# M8830Ccpld.net
KiCad netlist of a schematic drawn in EAGLE
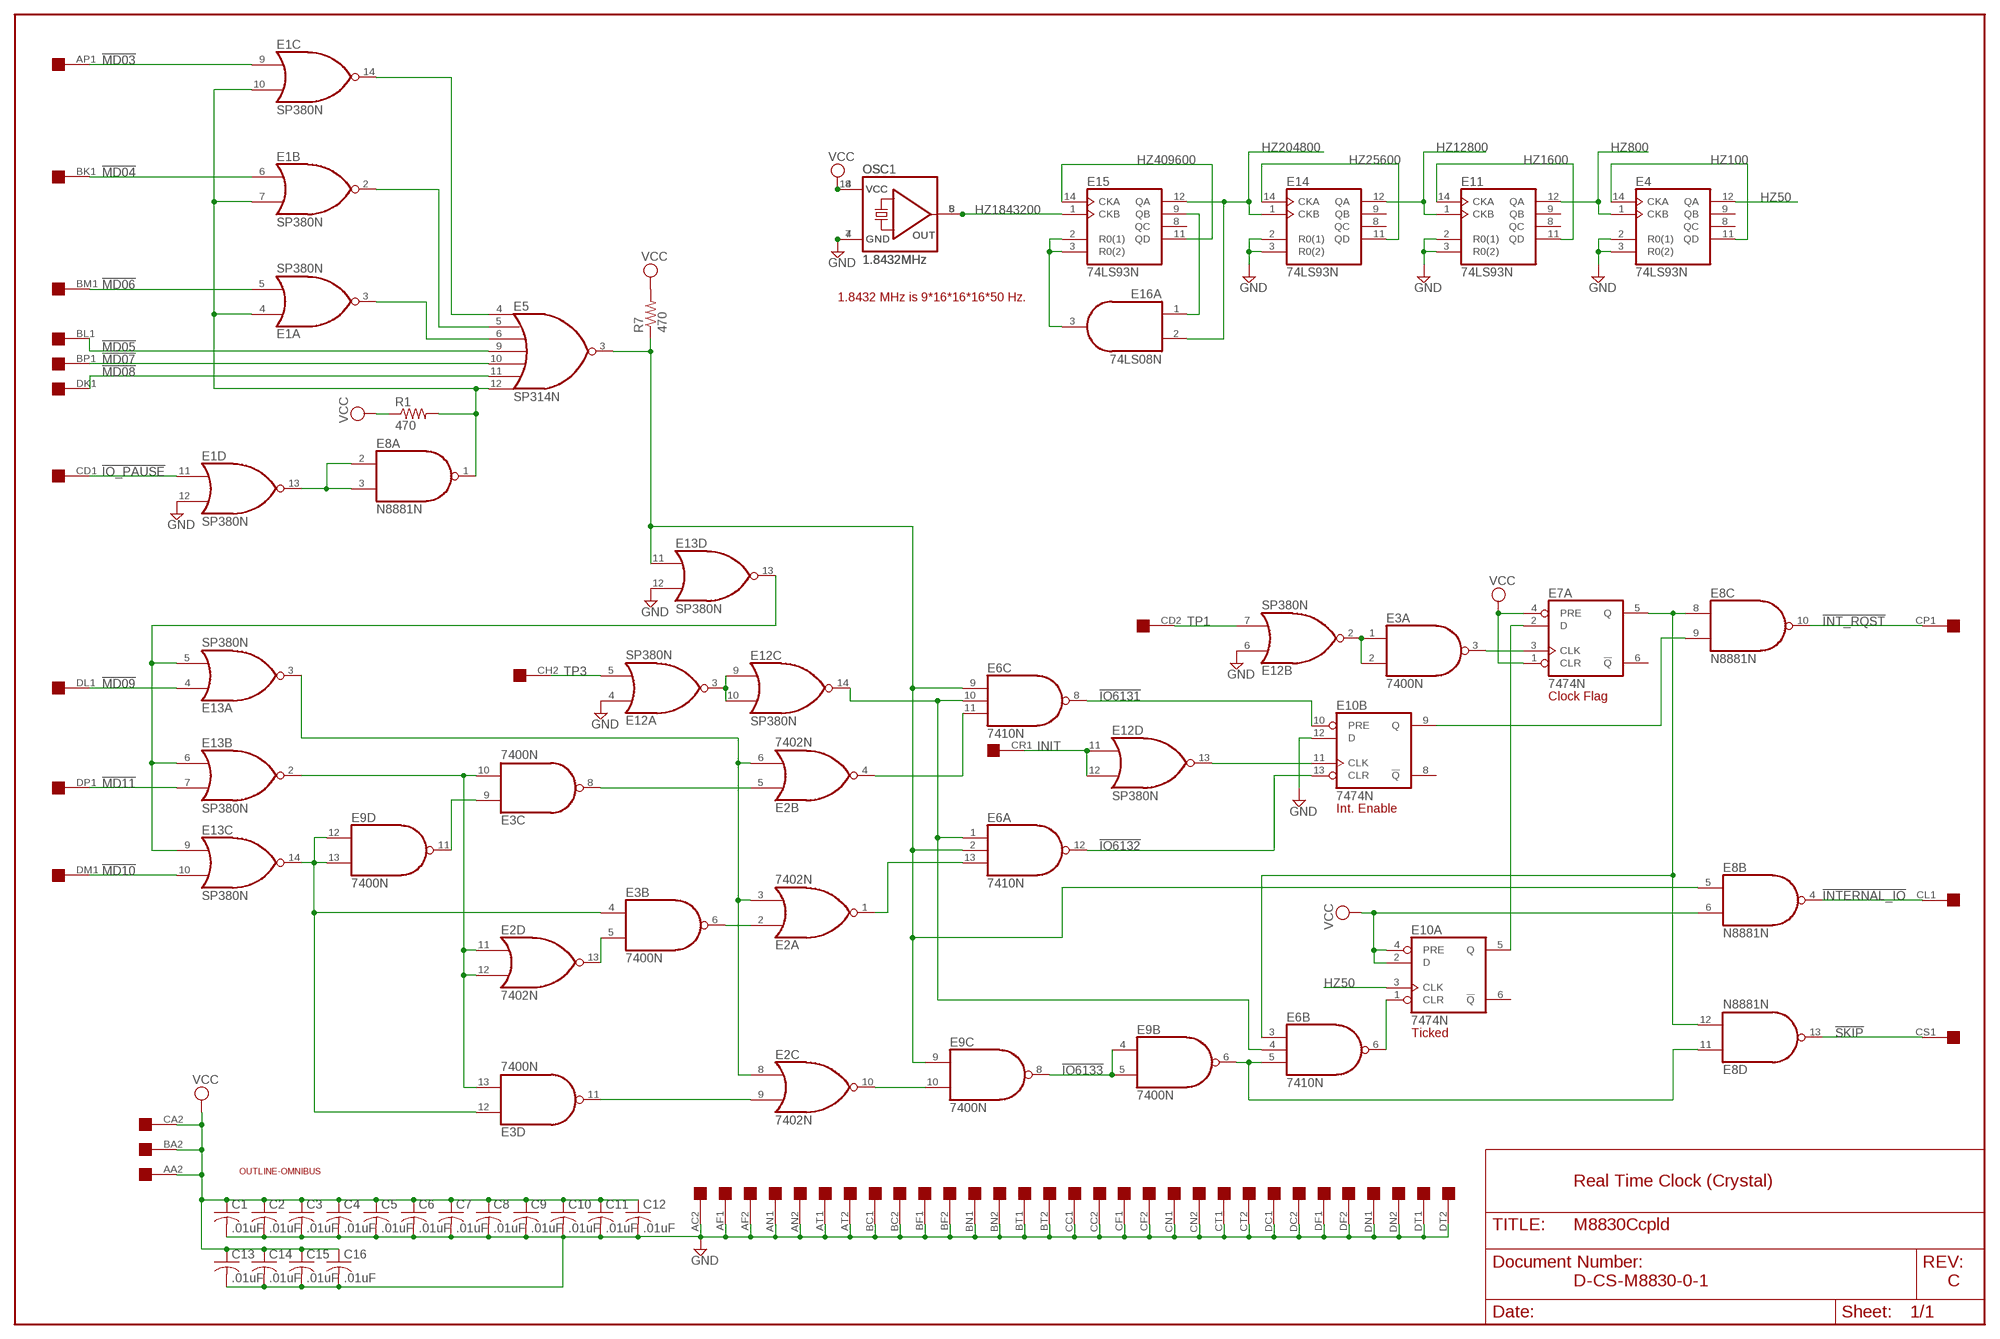
[diagram p0: schematic, sheet 1]

(export (version "E")
  (design (tool "Eeschema 10.0.6"))
  (components
    (comp (ref "C1")
      (value ".01uF")
      (footprint "eagle-import:C050-025X075")
      (libsource (lib "eagle-import") (part "C-US050-025X075"))
    )
    (comp (ref "C2")
      (value ".01uF")
      (footprint "eagle-import:C050-025X075")
      (libsource (lib "eagle-import") (part "C-US050-025X075"))
    )
    (comp (ref "C3")
      (value ".01uF")
      (footprint "eagle-import:C050-025X075")
      (libsource (lib "eagle-import") (part "C-US050-025X075"))
    )
    (comp (ref "C4")
      (value ".01uF")
      (footprint "eagle-import:C050-025X075")
      (libsource (lib "eagle-import") (part "C-US050-025X075"))
    )
    (comp (ref "C5")
      (value ".01uF")
      (footprint "eagle-import:C050-025X075")
      (libsource (lib "eagle-import") (part "C-US050-025X075"))
    )
    (comp (ref "C6")
      (value ".01uF")
      (footprint "eagle-import:C050-025X075")
      (libsource (lib "eagle-import") (part "C-US050-025X075"))
    )
    (comp (ref "C7")
      (value ".01uF")
      (footprint "eagle-import:C050-025X075")
      (libsource (lib "eagle-import") (part "C-US050-025X075"))
    )
    (comp (ref "C8")
      (value ".01uF")
      (footprint "eagle-import:C050-025X075")
      (libsource (lib "eagle-import") (part "C-US050-025X075"))
    )
    (comp (ref "C9")
      (value ".01uF")
      (footprint "eagle-import:C050-025X075")
      (libsource (lib "eagle-import") (part "C-US050-025X075"))
    )
    (comp (ref "C10")
      (value ".01uF")
      (footprint "eagle-import:C050-025X075")
      (libsource (lib "eagle-import") (part "C-US050-025X075"))
    )
    (comp (ref "C11")
      (value ".01uF")
      (footprint "eagle-import:C050-025X075")
      (libsource (lib "eagle-import") (part "C-US050-025X075"))
    )
    (comp (ref "C12")
      (value ".01uF")
      (footprint "eagle-import:C050-025X075")
      (libsource (lib "eagle-import") (part "C-US050-025X075"))
    )
    (comp (ref "C13")
      (value ".01uF")
      (footprint "eagle-import:C050-025X075")
      (libsource (lib "eagle-import") (part "C-US050-025X075"))
    )
    (comp (ref "C14")
      (value ".01uF")
      (footprint "eagle-import:C050-025X075")
      (libsource (lib "eagle-import") (part "C-US050-025X075"))
    )
    (comp (ref "C15")
      (value ".01uF")
      (footprint "eagle-import:C050-025X075")
      (libsource (lib "eagle-import") (part "C-US050-025X075"))
    )
    (comp (ref "C16")
      (value ".01uF")
      (footprint "eagle-import:C050-025X075")
      (libsource (lib "eagle-import") (part "C-US050-025X075"))
    )
    (comp (ref "E1")
      (value "SP380N")
      (footprint "eagle-import:DIL14")
      (libsource (lib "eagle-import") (part "SP380N"))
    )
    (comp (ref "E2")
      (value "7402N")
      (footprint "eagle-import:DIL14")
      (libsource (lib "eagle-import") (part "7402N"))
    )
    (comp (ref "E3")
      (value "7400N")
      (footprint "eagle-import:DIL14")
      (libsource (lib "eagle-import") (part "7400N"))
    )
    (comp (ref "E4")
      (value "74LS93N")
      (footprint "eagle-import:DIL14")
      (libsource (lib "eagle-import") (part "7493NLS"))
    )
    (comp (ref "E5")
      (value "SP314N")
      (footprint "eagle-import:DIL14")
      (libsource (lib "eagle-import") (part "SP314N"))
    )
    (comp (ref "E6")
      (value "7410N")
      (footprint "eagle-import:DIL14")
      (libsource (lib "eagle-import") (part "7410N"))
    )
    (comp (ref "E7")
      (value "7474N")
      (footprint "eagle-import:DIL14")
      (libsource (lib "eagle-import") (part "7474NS"))
    )
    (comp (ref "E8")
      (value "N8881N")
      (footprint "eagle-import:DIL14")
      (libsource (lib "eagle-import") (part "N8881N"))
    )
    (comp (ref "E9")
      (value "7400N")
      (footprint "eagle-import:DIL14")
      (libsource (lib "eagle-import") (part "7400N"))
    )
    (comp (ref "E10")
      (value "7474N")
      (footprint "eagle-import:DIL14")
      (libsource (lib "eagle-import") (part "7474NS"))
    )
    (comp (ref "E11")
      (value "74LS93N")
      (footprint "eagle-import:DIL14")
      (libsource (lib "eagle-import") (part "7493NLS"))
    )
    (comp (ref "E12")
      (value "SP380N")
      (footprint "eagle-import:DIL14")
      (libsource (lib "eagle-import") (part "SP380N"))
    )
    (comp (ref "E13")
      (value "SP380N")
      (footprint "eagle-import:DIL14")
      (libsource (lib "eagle-import") (part "SP380N"))
    )
    (comp (ref "E14")
      (value "74LS93N")
      (footprint "eagle-import:DIL14")
      (libsource (lib "eagle-import") (part "7493NLS"))
    )
    (comp (ref "E15")
      (value "74LS93N")
      (footprint "eagle-import:DIL14")
      (libsource (lib "eagle-import") (part "7493NLS"))
    )
    (comp (ref "E16")
      (value "74LS08N")
      (footprint "eagle-import:DIL14")
      (libsource (lib "eagle-import") (part "7408NLS"))
    )
    (comp (ref "EDGE")
      (value "QUAD")
      (footprint "eagle-import:EDGE-CON8")
      (libsource (lib "eagle-import") (part "QUAD"))
    )
    (comp (ref "OSC")
      (value "1.8432MHz")
      (footprint "eagle-import:DIL08S")
      (libsource (lib "eagle-import") (part "QG5460"))
    )
    (comp (ref "OSC1")
      (value "1.8432MHz")
      (footprint "eagle-import:DIL14S")
      (libsource (lib "eagle-import") (part "QG5860"))
    )
    (comp (ref "R1")
      (value "470")
      (footprint "eagle-import:0207_10")
      (libsource (lib "eagle-import") (part "R-US_0207/10"))
    )
    (comp (ref "R7")
      (value "470")
      (footprint "eagle-import:0207_10")
      (libsource (lib "eagle-import") (part "R-US_0207/10"))
    )
    (comp (ref "U$1")
      (value "OUTLINE-OMNIBUS")
      (footprint "eagle-import:OMNIBUS")
      (libsource (lib "eagle-import") (part "OUTLINE-OMNIBUS"))
    )
  )
  (nets
    (net (code "1") (name "/HZ50") (class "Default")
      (node (ref "E10") (pin "3") (pinfunction "CLK_3") (pintype "input"))
      (node (ref "E4") (pin "12") (pinfunction "QA_12") (pintype "output"))
    )
    (net (code "2") (name "/HZ100") (class "Default")
      (node (ref "E4") (pin "11") (pinfunction "QD_11") (pintype "output"))
      (node (ref "E4") (pin "14") (pinfunction "CKA_14") (pintype "input"))
    )
    (net (code "3") (name "/HZ800") (class "Default")
      (node (ref "E11") (pin "12") (pinfunction "QA_12") (pintype "output"))
      (node (ref "E4") (pin "1") (pinfunction "CKB_1") (pintype "input"))
    )
    (net (code "4") (name "/HZ1600") (class "Default")
      (node (ref "E11") (pin "11") (pinfunction "QD_11") (pintype "output"))
      (node (ref "E11") (pin "14") (pinfunction "CKA_14") (pintype "input"))
    )
    (net (code "5") (name "/HZ12800") (class "Default")
      (node (ref "E11") (pin "1") (pinfunction "CKB_1") (pintype "input"))
      (node (ref "E14") (pin "12") (pinfunction "QA_12") (pintype "output"))
    )
    (net (code "6") (name "/HZ25600") (class "Default")
      (node (ref "E14") (pin "11") (pinfunction "QD_11") (pintype "output"))
      (node (ref "E14") (pin "14") (pinfunction "CKA_14") (pintype "input"))
    )
    (net (code "7") (name "/HZ204800") (class "Default")
      (node (ref "E14") (pin "1") (pinfunction "CKB_1") (pintype "input"))
      (node (ref "E15") (pin "12") (pinfunction "QA_12") (pintype "output"))
      (node (ref "E16") (pin "2") (pinfunction "I1_2") (pintype "input"))
    )
    (net (code "8") (name "/HZ409600") (class "Default")
      (node (ref "E15") (pin "11") (pinfunction "QD_11") (pintype "output"))
      (node (ref "E15") (pin "14") (pinfunction "CKA_14") (pintype "input"))
    )
    (net (code "9") (name "/HZ1843200") (class "Default")
      (node (ref "E15") (pin "1") (pinfunction "CKB_1") (pintype "input"))
      (node (ref "OSC") (pin "5") (pinfunction "OUT_5") (pintype "output"))
      (node (ref "OSC1") (pin "8") (pinfunction "OUT_8") (pintype "output"))
    )
    (net (code "10") (name "/INIT") (class "Default")
      (node (ref "E12") (pin "11") (pinfunction "I0_11") (pintype "input"))
      (node (ref "E12") (pin "12") (pinfunction "I1_12") (pintype "input"))
      (node (ref "EDGE") (pin "CR1") (pinfunction "1_CR1") (pintype "bidirectional"))
    )
    (net (code "11") (name "/TP1") (class "Default")
      (node (ref "E12") (pin "7") (pinfunction "I1_7") (pintype "input"))
      (node (ref "EDGE") (pin "CD2") (pinfunction "1_CD2") (pintype "bidirectional"))
    )
    (net (code "12") (name "/TP3") (class "Default")
      (node (ref "E12") (pin "5") (pinfunction "I1_5") (pintype "input"))
      (node (ref "EDGE") (pin "CH2") (pinfunction "1_CH2") (pintype "bidirectional"))
    )
    (net (code "13") (name "/~{INTERNAL_IO}") (class "Default")
      (node (ref "E8") (pin "4") (pinfunction "O_4") (pintype "open_collector"))
      (node (ref "EDGE") (pin "CL1") (pinfunction "1_CL1") (pintype "bidirectional"))
    )
    (net (code "14") (name "/~{INT_RQST}") (class "Default")
      (node (ref "E8") (pin "10") (pinfunction "O_10") (pintype "open_collector"))
      (node (ref "EDGE") (pin "CP1") (pinfunction "1_CP1") (pintype "bidirectional"))
    )
    (net (code "15") (name "/~{IO6131}") (class "Default")
      (node (ref "E10") (pin "10") (pinfunction "PRE_10") (pintype "input"))
      (node (ref "E6") (pin "8") (pinfunction "O_8") (pintype "output"))
    )
    (net (code "16") (name "/~{IO6132}") (class "Default")
      (node (ref "E10") (pin "13") (pinfunction "CLR_13") (pintype "input"))
      (node (ref "E6") (pin "12") (pinfunction "O_12") (pintype "output"))
    )
    (net (code "17") (name "/~{IO6133}") (class "Default")
      (node (ref "E9") (pin "4") (pinfunction "I0_4") (pintype "input"))
      (node (ref "E9") (pin "5") (pinfunction "I1_5") (pintype "input"))
      (node (ref "E9") (pin "8") (pinfunction "O_8") (pintype "output"))
    )
    (net (code "18") (name "/~{IO_PAUSE}") (class "Default")
      (node (ref "E1") (pin "11") (pinfunction "I0_11") (pintype "input"))
      (node (ref "EDGE") (pin "CD1") (pinfunction "1_CD1") (pintype "bidirectional"))
    )
    (net (code "19") (name "/~{MD03}") (class "Default")
      (node (ref "E1") (pin "9") (pinfunction "I0_9") (pintype "input"))
      (node (ref "EDGE") (pin "AP1") (pinfunction "1_AP1") (pintype "bidirectional"))
    )
    (net (code "20") (name "/~{MD04}") (class "Default")
      (node (ref "E1") (pin "6") (pinfunction "I0_6") (pintype "input"))
      (node (ref "EDGE") (pin "BK1") (pinfunction "1_BK1") (pintype "bidirectional"))
    )
    (net (code "21") (name "/~{MD05}") (class "Default")
      (node (ref "E5") (pin "9") (pinfunction "I3_9") (pintype "input"))
      (node (ref "EDGE") (pin "BL1") (pinfunction "1_BL1") (pintype "bidirectional"))
    )
    (net (code "22") (name "/~{MD06}") (class "Default")
      (node (ref "E1") (pin "5") (pinfunction "I1_5") (pintype "input"))
      (node (ref "EDGE") (pin "BM1") (pinfunction "1_BM1") (pintype "bidirectional"))
    )
    (net (code "23") (name "/~{MD07}") (class "Default")
      (node (ref "E5") (pin "10") (pinfunction "I4_10") (pintype "input"))
      (node (ref "EDGE") (pin "BP1") (pinfunction "1_BP1") (pintype "bidirectional"))
    )
    (net (code "24") (name "/~{MD08}") (class "Default")
      (node (ref "E5") (pin "11") (pinfunction "I5_11") (pintype "input"))
      (node (ref "EDGE") (pin "DK1") (pinfunction "1_DK1") (pintype "bidirectional"))
    )
    (net (code "25") (name "/~{MD09}") (class "Default")
      (node (ref "E13") (pin "4") (pinfunction "I0_4") (pintype "input"))
      (node (ref "EDGE") (pin "DL1") (pinfunction "1_DL1") (pintype "bidirectional"))
    )
    (net (code "26") (name "/~{MD10}") (class "Default")
      (node (ref "E13") (pin "10") (pinfunction "I1_10") (pintype "input"))
      (node (ref "EDGE") (pin "DM1") (pinfunction "1_DM1") (pintype "bidirectional"))
    )
    (net (code "27") (name "/~{MD11}") (class "Default")
      (node (ref "E13") (pin "7") (pinfunction "I1_7") (pintype "input"))
      (node (ref "EDGE") (pin "DP1") (pinfunction "1_DP1") (pintype "bidirectional"))
    )
    (net (code "28") (name "/~{SKIP}") (class "Default")
      (node (ref "E8") (pin "13") (pinfunction "O_13") (pintype "open_collector"))
      (node (ref "EDGE") (pin "CS1") (pinfunction "1_CS1") (pintype "bidirectional"))
    )
    (net (code "29") (name "GND") (class "Default")
      (node (ref "C1") (pin "2") (pinfunction "2_2") (pintype "passive"))
      (node (ref "C10") (pin "2") (pinfunction "2_2") (pintype "passive"))
      (node (ref "C11") (pin "2") (pinfunction "2_2") (pintype "passive"))
      (node (ref "C12") (pin "2") (pinfunction "2_2") (pintype "passive"))
      (node (ref "C13") (pin "2") (pinfunction "2_2") (pintype "passive"))
      (node (ref "C14") (pin "2") (pinfunction "2_2") (pintype "passive"))
      (node (ref "C15") (pin "2") (pinfunction "2_2") (pintype "passive"))
      (node (ref "C16") (pin "2") (pinfunction "2_2") (pintype "passive"))
      (node (ref "C2") (pin "2") (pinfunction "2_2") (pintype "passive"))
      (node (ref "C3") (pin "2") (pinfunction "2_2") (pintype "passive"))
      (node (ref "C4") (pin "2") (pinfunction "2_2") (pintype "passive"))
      (node (ref "C5") (pin "2") (pinfunction "2_2") (pintype "passive"))
      (node (ref "C6") (pin "2") (pinfunction "2_2") (pintype "passive"))
      (node (ref "C7") (pin "2") (pinfunction "2_2") (pintype "passive"))
      (node (ref "C8") (pin "2") (pinfunction "2_2") (pintype "passive"))
      (node (ref "C9") (pin "2") (pinfunction "2_2") (pintype "passive"))
      (node (ref "E1") (pin "12") (pinfunction "I1_12") (pintype "input"))
      (node (ref "E10") (pin "12") (pinfunction "D_12") (pintype "input"))
      (node (ref "E11") (pin "2") (pinfunction "R0(1)_2") (pintype "input"))
      (node (ref "E11") (pin "3") (pinfunction "R0(2)_3") (pintype "input"))
      (node (ref "E12") (pin "4") (pinfunction "I0_4") (pintype "input"))
      (node (ref "E12") (pin "6") (pinfunction "I0_6") (pintype "input"))
      (node (ref "E13") (pin "12") (pinfunction "I1_12") (pintype "input"))
      (node (ref "E14") (pin "2") (pinfunction "R0(1)_2") (pintype "input"))
      (node (ref "E14") (pin "3") (pinfunction "R0(2)_3") (pintype "input"))
      (node (ref "E4") (pin "2") (pinfunction "R0(1)_2") (pintype "input"))
      (node (ref "E4") (pin "3") (pinfunction "R0(2)_3") (pintype "input"))
      (node (ref "EDGE") (pin "AC2") (pinfunction "1_AC2") (pintype "bidirectional"))
      (node (ref "EDGE") (pin "AF1") (pinfunction "1_AF1") (pintype "bidirectional"))
      (node (ref "EDGE") (pin "AF2") (pinfunction "1_AF2") (pintype "bidirectional"))
      (node (ref "EDGE") (pin "AN1") (pinfunction "1_AN1") (pintype "bidirectional"))
      (node (ref "EDGE") (pin "AN2") (pinfunction "1_AN2") (pintype "bidirectional"))
      (node (ref "EDGE") (pin "AT1") (pinfunction "1_AT1") (pintype "bidirectional"))
      (node (ref "EDGE") (pin "AT2") (pinfunction "1_AT2") (pintype "bidirectional"))
      (node (ref "EDGE") (pin "BC1") (pinfunction "1_BC1") (pintype "bidirectional"))
      (node (ref "EDGE") (pin "BC2") (pinfunction "1_BC2") (pintype "bidirectional"))
      (node (ref "EDGE") (pin "BF1") (pinfunction "1_BF1") (pintype "bidirectional"))
      (node (ref "EDGE") (pin "BF2") (pinfunction "1_BF2") (pintype "bidirectional"))
      (node (ref "EDGE") (pin "BN1") (pinfunction "1_BN1") (pintype "bidirectional"))
      (node (ref "EDGE") (pin "BN2") (pinfunction "1_BN2") (pintype "bidirectional"))
      (node (ref "EDGE") (pin "BT1") (pinfunction "1_BT1") (pintype "bidirectional"))
      (node (ref "EDGE") (pin "BT2") (pinfunction "1_BT2") (pintype "bidirectional"))
      (node (ref "EDGE") (pin "CC1") (pinfunction "1_CC1") (pintype "bidirectional"))
      (node (ref "EDGE") (pin "CC2") (pinfunction "1_CC2") (pintype "bidirectional"))
      (node (ref "EDGE") (pin "CF1") (pinfunction "1_CF1") (pintype "bidirectional"))
      (node (ref "EDGE") (pin "CF2") (pinfunction "1_CF2") (pintype "bidirectional"))
      (node (ref "EDGE") (pin "CN1") (pinfunction "1_CN1") (pintype "bidirectional"))
      (node (ref "EDGE") (pin "CN2") (pinfunction "1_CN2") (pintype "bidirectional"))
      (node (ref "EDGE") (pin "CT1") (pinfunction "1_CT1") (pintype "bidirectional"))
      (node (ref "EDGE") (pin "CT2") (pinfunction "1_CT2") (pintype "bidirectional"))
      (node (ref "EDGE") (pin "DC1") (pinfunction "1_DC1") (pintype "bidirectional"))
      (node (ref "EDGE") (pin "DC2") (pinfunction "1_DC2") (pintype "bidirectional"))
      (node (ref "EDGE") (pin "DF1") (pinfunction "1_DF1") (pintype "bidirectional"))
      (node (ref "EDGE") (pin "DF2") (pinfunction "1_DF2") (pintype "bidirectional"))
      (node (ref "EDGE") (pin "DN1") (pinfunction "1_DN1") (pintype "bidirectional"))
      (node (ref "EDGE") (pin "DN2") (pinfunction "1_DN2") (pintype "bidirectional"))
      (node (ref "EDGE") (pin "DT1") (pinfunction "1_DT1") (pintype "bidirectional"))
      (node (ref "EDGE") (pin "DT2") (pinfunction "1_DT2") (pintype "bidirectional"))
      (node (ref "OSC") (pin "4") (pinfunction "GND_4") (pintype "power_in"))
      (node (ref "OSC1") (pin "7") (pinfunction "GND_7") (pintype "power_in"))
    )
    (net (code "30") (name "Net-(E1A-I0)") (class "Default")
      (node (ref "E1") (pin "10") (pinfunction "I1_10") (pintype "input"))
      (node (ref "E1") (pin "4") (pinfunction "I0_4") (pintype "input"))
      (node (ref "E1") (pin "7") (pinfunction "I1_7") (pintype "input"))
      (node (ref "E5") (pin "12") (pinfunction "I6_12") (pintype "input"))
      (node (ref "E8") (pin "1") (pinfunction "O_1") (pintype "open_collector"))
      (node (ref "R1") (pin "2") (pinfunction "2_2") (pintype "passive"))
    )
    (net (code "31") (name "Net-(E1A-O)") (class "Default")
      (node (ref "E1") (pin "3") (pinfunction "O_3") (pintype "output"))
      (node (ref "E5") (pin "6") (pinfunction "I2_6") (pintype "input"))
    )
    (net (code "32") (name "Net-(E1B-O)") (class "Default")
      (node (ref "E1") (pin "2") (pinfunction "O_2") (pintype "output"))
      (node (ref "E5") (pin "5") (pinfunction "I1_5") (pintype "input"))
    )
    (net (code "33") (name "Net-(E1C-O)") (class "Default")
      (node (ref "E1") (pin "14") (pinfunction "O_14") (pintype "output"))
      (node (ref "E5") (pin "4") (pinfunction "I0_4") (pintype "input"))
    )
    (net (code "34") (name "Net-(E1D-O)") (class "Default")
      (node (ref "E1") (pin "13") (pinfunction "O_13") (pintype "output"))
      (node (ref "E8") (pin "2") (pinfunction "I0_2") (pintype "input"))
      (node (ref "E8") (pin "3") (pinfunction "I1_3") (pintype "input"))
    )
    (net (code "35") (name "Net-(E2A-I0)") (class "Default")
      (node (ref "E2") (pin "2") (pinfunction "I0_2") (pintype "input"))
      (node (ref "E3") (pin "6") (pinfunction "O_6") (pintype "output"))
    )
    (net (code "36") (name "Net-(E2A-O)") (class "Default")
      (node (ref "E2") (pin "1") (pinfunction "O_1") (pintype "output"))
      (node (ref "E6") (pin "13") (pinfunction "I2_13") (pintype "input"))
    )
    (net (code "37") (name "Net-(E2B-I0)") (class "Default")
      (node (ref "E2") (pin "5") (pinfunction "I0_5") (pintype "input"))
      (node (ref "E3") (pin "8") (pinfunction "O_8") (pintype "output"))
    )
    (net (code "38") (name "Net-(E2B-O)") (class "Default")
      (node (ref "E2") (pin "4") (pinfunction "O_4") (pintype "output"))
      (node (ref "E6") (pin "11") (pinfunction "I2_11") (pintype "input"))
    )
    (net (code "39") (name "Net-(E2C-I1)") (class "Default")
      (node (ref "E2") (pin "9") (pinfunction "I1_9") (pintype "input"))
      (node (ref "E3") (pin "11") (pinfunction "O_11") (pintype "output"))
    )
    (net (code "40") (name "Net-(E2C-O)") (class "Default")
      (node (ref "E2") (pin "10") (pinfunction "O_10") (pintype "output"))
      (node (ref "E9") (pin "10") (pinfunction "I1_10") (pintype "input"))
    )
    (net (code "41") (name "Net-(E2D-O)") (class "Default")
      (node (ref "E2") (pin "13") (pinfunction "O_13") (pintype "output"))
      (node (ref "E3") (pin "5") (pinfunction "I1_5") (pintype "input"))
    )
    (net (code "42") (name "Net-(E3A-O)") (class "Default")
      (node (ref "E3") (pin "3") (pinfunction "O_3") (pintype "output"))
      (node (ref "E7") (pin "3") (pinfunction "CLK_3") (pintype "input"))
    )
    (net (code "43") (name "Net-(E3C-I0)") (class "Default")
      (node (ref "E3") (pin "9") (pinfunction "I0_9") (pintype "input"))
      (node (ref "E9") (pin "11") (pinfunction "O_11") (pintype "output"))
    )
    (net (code "44") (name "Net-(E6B-I0)") (class "Default")
      (node (ref "E6") (pin "3") (pinfunction "I0_3") (pintype "input"))
      (node (ref "E7") (pin "5") (pinfunction "Q_5") (pintype "output"))
      (node (ref "E8") (pin "12") (pinfunction "I1_12") (pintype "input"))
      (node (ref "E8") (pin "8") (pinfunction "I0_8") (pintype "input"))
    )
    (net (code "45") (name "Net-(E6B-I2)") (class "Default")
      (node (ref "E6") (pin "5") (pinfunction "I2_5") (pintype "input"))
      (node (ref "E8") (pin "11") (pinfunction "I0_11") (pintype "input"))
      (node (ref "E9") (pin "6") (pinfunction "O_6") (pintype "output"))
    )
    (net (code "46") (name "Net-(E10A-CLR)") (class "Default")
      (node (ref "E10") (pin "1") (pinfunction "CLR_1") (pintype "input"))
      (node (ref "E6") (pin "6") (pinfunction "O_6") (pintype "output"))
    )
    (net (code "47") (name "Net-(E10A-Q)") (class "Default")
      (node (ref "E10") (pin "5") (pinfunction "Q_5") (pintype "output"))
      (node (ref "E7") (pin "2") (pinfunction "D_2") (pintype "input"))
    )
    (net (code "48") (name "Net-(E10B-CLK)") (class "Default")
      (node (ref "E10") (pin "11") (pinfunction "CLK_11") (pintype "input"))
      (node (ref "E12") (pin "13") (pinfunction "O_13") (pintype "output"))
    )
    (net (code "49") (name "Net-(E10B-Q)") (class "Default")
      (node (ref "E10") (pin "9") (pinfunction "Q_9") (pintype "output"))
      (node (ref "E8") (pin "9") (pinfunction "I1_9") (pintype "input"))
    )
    (net (code "50") (name "Net-(E12A-O)") (class "Default")
      (node (ref "E12") (pin "10") (pinfunction "I1_10") (pintype "input"))
      (node (ref "E12") (pin "3") (pinfunction "O_3") (pintype "output"))
      (node (ref "E12") (pin "9") (pinfunction "I0_9") (pintype "input"))
    )
    (net (code "51") (name "Net-(E12B-O)") (class "Default")
      (node (ref "E12") (pin "2") (pinfunction "O_2") (pintype "output"))
      (node (ref "E3") (pin "1") (pinfunction "I0_1") (pintype "input"))
      (node (ref "E3") (pin "2") (pinfunction "I1_2") (pintype "input"))
    )
    (net (code "52") (name "Net-(E12C-O)") (class "Default")
      (node (ref "E12") (pin "14") (pinfunction "O_14") (pintype "output"))
      (node (ref "E6") (pin "1") (pinfunction "I0_1") (pintype "input"))
      (node (ref "E6") (pin "10") (pinfunction "I1_10") (pintype "input"))
      (node (ref "E6") (pin "4") (pinfunction "I1_4") (pintype "input"))
    )
    (net (code "53") (name "Net-(E13A-I1)") (class "Default")
      (node (ref "E13") (pin "13") (pinfunction "O_13") (pintype "output"))
      (node (ref "E13") (pin "5") (pinfunction "I1_5") (pintype "input"))
      (node (ref "E13") (pin "6") (pinfunction "I0_6") (pintype "input"))
      (node (ref "E13") (pin "9") (pinfunction "I0_9") (pintype "input"))
    )
    (net (code "54") (name "Net-(E13A-O)") (class "Default")
      (node (ref "E13") (pin "3") (pinfunction "O_3") (pintype "output"))
      (node (ref "E2") (pin "3") (pinfunction "I1_3") (pintype "input"))
      (node (ref "E2") (pin "6") (pinfunction "I1_6") (pintype "input"))
      (node (ref "E2") (pin "8") (pinfunction "I0_8") (pintype "input"))
    )
    (net (code "55") (name "Net-(E13B-O)") (class "Default")
      (node (ref "E13") (pin "2") (pinfunction "O_2") (pintype "output"))
      (node (ref "E2") (pin "11") (pinfunction "I0_11") (pintype "input"))
      (node (ref "E2") (pin "12") (pinfunction "I1_12") (pintype "input"))
      (node (ref "E3") (pin "10") (pinfunction "I1_10") (pintype "input"))
      (node (ref "E3") (pin "13") (pinfunction "I1_13") (pintype "input"))
    )
    (net (code "56") (name "Net-(E13C-O)") (class "Default")
      (node (ref "E13") (pin "14") (pinfunction "O_14") (pintype "output"))
      (node (ref "E3") (pin "12") (pinfunction "I0_12") (pintype "input"))
      (node (ref "E3") (pin "4") (pinfunction "I0_4") (pintype "input"))
      (node (ref "E9") (pin "12") (pinfunction "I0_12") (pintype "input"))
      (node (ref "E9") (pin "13") (pinfunction "I1_13") (pintype "input"))
    )
    (net (code "57") (name "Net-(E13D-I0)") (class "Default")
      (node (ref "E13") (pin "11") (pinfunction "I0_11") (pintype "input"))
      (node (ref "E5") (pin "3") (pinfunction "O_3") (pintype "output"))
      (node (ref "E6") (pin "2") (pinfunction "I1_2") (pintype "input"))
      (node (ref "E6") (pin "9") (pinfunction "I0_9") (pintype "input"))
      (node (ref "E8") (pin "5") (pinfunction "I0_5") (pintype "input"))
      (node (ref "E9") (pin "9") (pinfunction "I0_9") (pintype "input"))
      (node (ref "R7") (pin "1") (pinfunction "1_1") (pintype "passive"))
    )
    (net (code "58") (name "Net-(E15A-QB)") (class "Default")
      (node (ref "E15") (pin "9") (pinfunction "QB_9") (pintype "output"))
      (node (ref "E16") (pin "1") (pinfunction "I0_1") (pintype "input"))
    )
    (net (code "59") (name "Net-(E15A-R0(1))") (class "Default")
      (node (ref "E15") (pin "2") (pinfunction "R0(1)_2") (pintype "input"))
      (node (ref "E15") (pin "3") (pinfunction "R0(2)_3") (pintype "input"))
      (node (ref "E16") (pin "3") (pinfunction "O_3") (pintype "output"))
    )
    (net (code "60") (name "VCC") (class "Default")
      (node (ref "C1") (pin "1") (pinfunction "1_1") (pintype "passive"))
      (node (ref "C10") (pin "1") (pinfunction "1_1") (pintype "passive"))
      (node (ref "C11") (pin "1") (pinfunction "1_1") (pintype "passive"))
      (node (ref "C12") (pin "1") (pinfunction "1_1") (pintype "passive"))
      (node (ref "C13") (pin "1") (pinfunction "1_1") (pintype "passive"))
      (node (ref "C14") (pin "1") (pinfunction "1_1") (pintype "passive"))
      (node (ref "C15") (pin "1") (pinfunction "1_1") (pintype "passive"))
      (node (ref "C16") (pin "1") (pinfunction "1_1") (pintype "passive"))
      (node (ref "C2") (pin "1") (pinfunction "1_1") (pintype "passive"))
      (node (ref "C3") (pin "1") (pinfunction "1_1") (pintype "passive"))
      (node (ref "C4") (pin "1") (pinfunction "1_1") (pintype "passive"))
      (node (ref "C5") (pin "1") (pinfunction "1_1") (pintype "passive"))
      (node (ref "C6") (pin "1") (pinfunction "1_1") (pintype "passive"))
      (node (ref "C7") (pin "1") (pinfunction "1_1") (pintype "passive"))
      (node (ref "C8") (pin "1") (pinfunction "1_1") (pintype "passive"))
      (node (ref "C9") (pin "1") (pinfunction "1_1") (pintype "passive"))
      (node (ref "E10") (pin "2") (pinfunction "D_2") (pintype "input"))
      (node (ref "E10") (pin "4") (pinfunction "PRE_4") (pintype "input"))
      (node (ref "E7") (pin "1") (pinfunction "CLR_1") (pintype "input"))
      (node (ref "E7") (pin "4") (pinfunction "PRE_4") (pintype "input"))
      (node (ref "E8") (pin "6") (pinfunction "I1_6") (pintype "input"))
      (node (ref "EDGE") (pin "AA2") (pinfunction "1_AA2") (pintype "bidirectional"))
      (node (ref "EDGE") (pin "BA2") (pinfunction "1_BA2") (pintype "bidirectional"))
      (node (ref "EDGE") (pin "CA2") (pinfunction "1_CA2") (pintype "bidirectional"))
      (node (ref "OSC") (pin "8") (pinfunction "VCC_8") (pintype "power_in"))
      (node (ref "OSC1") (pin "14") (pinfunction "VCC_14") (pintype "power_in"))
      (node (ref "R1") (pin "1") (pinfunction "1_1") (pintype "passive"))
      (node (ref "R7") (pin "2") (pinfunction "2_2") (pintype "passive"))
    )
    (net (code "61") (name "unconnected-(E4A-QB-Pad9)") (class "Default")
      (node (ref "E4") (pin "9") (pinfunction "QB_9") (pintype "output"))
    )
    (net (code "62") (name "unconnected-(E4A-QC-Pad8)") (class "Default")
      (node (ref "E4") (pin "8") (pinfunction "QC_8") (pintype "output"))
    )
    (net (code "63") (name "unconnected-(E7A-~{Q}-Pad6)") (class "Default")
      (node (ref "E7") (pin "6") (pinfunction "~{Q}_6") (pintype "output"))
    )
    (net (code "64") (name "unconnected-(E10A-~{Q}-Pad6)") (class "Default")
      (node (ref "E10") (pin "6") (pinfunction "~{Q}_6") (pintype "output"))
    )
    (net (code "65") (name "unconnected-(E10B-~{Q}-Pad8)") (class "Default")
      (node (ref "E10") (pin "8") (pinfunction "~{Q}_8") (pintype "output"))
    )
    (net (code "66") (name "unconnected-(E11A-QB-Pad9)") (class "Default")
      (node (ref "E11") (pin "9") (pinfunction "QB_9") (pintype "output"))
    )
    (net (code "67") (name "unconnected-(E11A-QC-Pad8)") (class "Default")
      (node (ref "E11") (pin "8") (pinfunction "QC_8") (pintype "output"))
    )
    (net (code "68") (name "unconnected-(E14A-QB-Pad9)") (class "Default")
      (node (ref "E14") (pin "9") (pinfunction "QB_9") (pintype "output"))
    )
    (net (code "69") (name "unconnected-(E14A-QC-Pad8)") (class "Default")
      (node (ref "E14") (pin "8") (pinfunction "QC_8") (pintype "output"))
    )
    (net (code "70") (name "unconnected-(E15A-QC-Pad8)") (class "Default")
      (node (ref "E15") (pin "8") (pinfunction "QC_8") (pintype "output"))
    )
  )
)
